# Sheet_2.net
KiCad netlist of a schematic drawn in Altium Designer
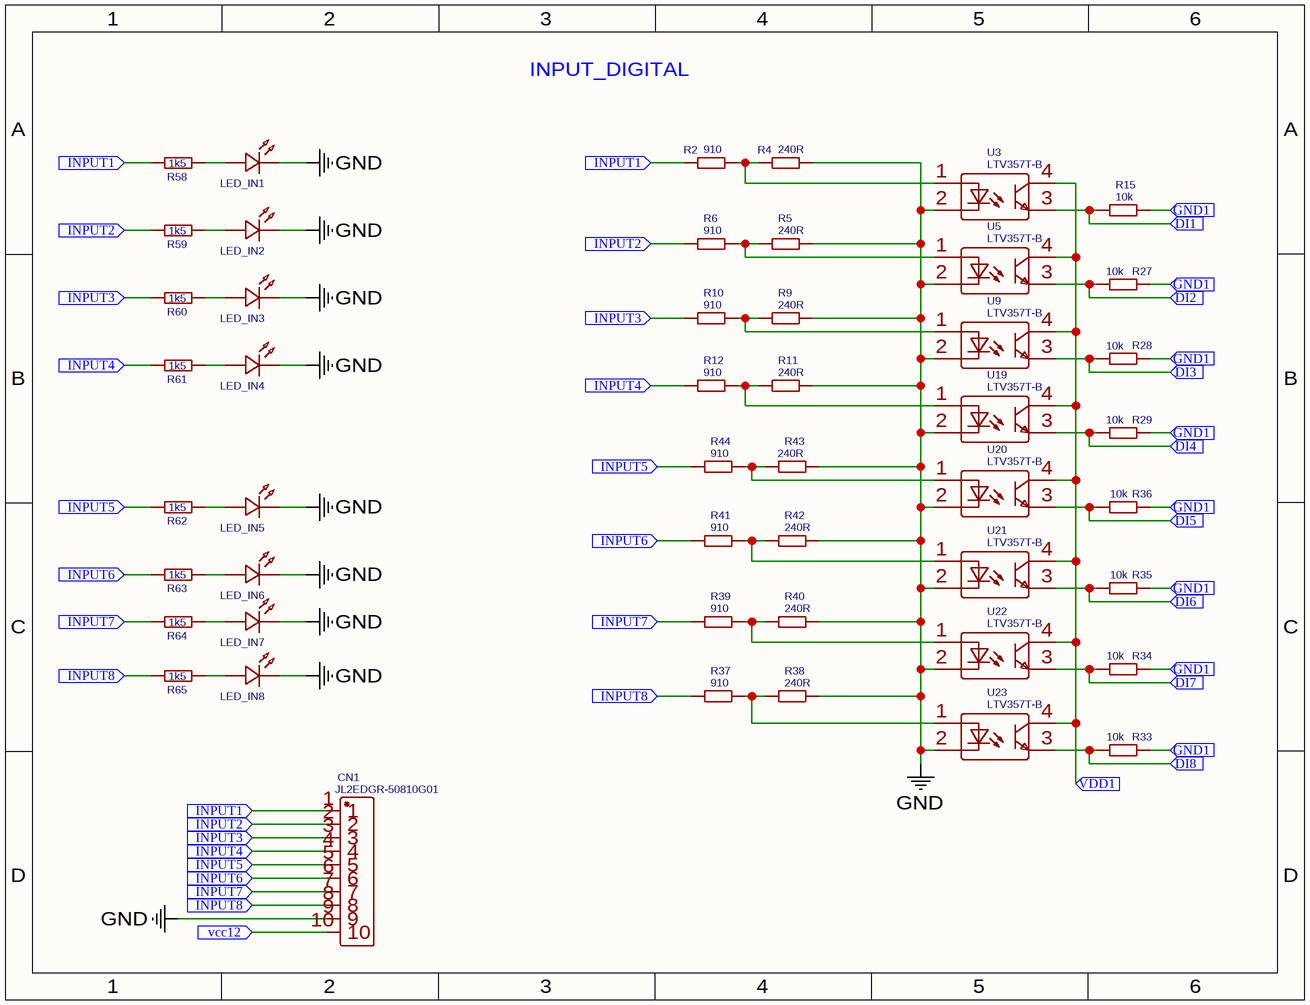
[diagram p0: Sheet_2.schdoc]

(export (version "E")
  (design (tool "Eeschema 10.0.6"))
  (components
    (comp (ref "CN1")
      (value "JL2EDGR-50810G01")
      (fields (field (name "BOM_SUPPLIER PART") "C424394") (field (name "CONTRIBUTOR") "LCSC"))
      (libsource (lib "altium-import") (part "root_0_JL2EDGR-50810G01_"))
    )
    (comp (ref "LED_IN1")
      (value "red")
      (fields
        (field (name "BOM_SUPPLIER PART") "C568941")
        (field (name "BOM_MANUFACTURER PART") "HL-503H3GD")
        (field (name "CONTRIBUTOR") "LCSC")
      )
      (libsource (lib "altium-import") (part "root_0_red_"))
    )
    (comp (ref "LED_IN2")
      (value "red")
      (fields
        (field (name "BOM_SUPPLIER PART") "C568941")
        (field (name "BOM_MANUFACTURER PART") "HL-503H3GD")
        (field (name "CONTRIBUTOR") "LCSC")
      )
      (libsource (lib "altium-import") (part "root_0_red_"))
    )
    (comp (ref "LED_IN3")
      (value "red")
      (fields
        (field (name "BOM_SUPPLIER PART") "C568941")
        (field (name "BOM_MANUFACTURER PART") "HL-503H3GD")
        (field (name "CONTRIBUTOR") "LCSC")
      )
      (libsource (lib "altium-import") (part "root_0_red_"))
    )
    (comp (ref "LED_IN4")
      (value "red")
      (fields
        (field (name "BOM_SUPPLIER PART") "C568941")
        (field (name "BOM_MANUFACTURER PART") "HL-503H3GD")
        (field (name "CONTRIBUTOR") "LCSC")
      )
      (libsource (lib "altium-import") (part "root_0_red_"))
    )
    (comp (ref "LED_IN5")
      (value "red")
      (fields
        (field (name "BOM_SUPPLIER PART") "C568941")
        (field (name "BOM_MANUFACTURER PART") "HL-503H3GD")
        (field (name "CONTRIBUTOR") "LCSC")
      )
      (libsource (lib "altium-import") (part "root_0_red_"))
    )
    (comp (ref "LED_IN6")
      (value "red")
      (fields
        (field (name "BOM_SUPPLIER PART") "C568941")
        (field (name "BOM_MANUFACTURER PART") "HL-503H3GD")
        (field (name "CONTRIBUTOR") "LCSC")
      )
      (libsource (lib "altium-import") (part "root_0_red_"))
    )
    (comp (ref "LED_IN7")
      (value "red")
      (fields
        (field (name "BOM_SUPPLIER PART") "C568941")
        (field (name "BOM_MANUFACTURER PART") "HL-503H3GD")
        (field (name "CONTRIBUTOR") "LCSC")
      )
      (libsource (lib "altium-import") (part "root_0_red_"))
    )
    (comp (ref "LED_IN8")
      (value "red")
      (fields
        (field (name "BOM_SUPPLIER PART") "C568941")
        (field (name "BOM_MANUFACTURER PART") "HL-503H3GD")
        (field (name "CONTRIBUTOR") "LCSC")
      )
      (libsource (lib "altium-import") (part "root_0_red_"))
    )
    (comp (ref "R2")
      (value "910")
      (fields (field (name "BOM_SUPPLIER PART") "C120038") (field (name "CONTRIBUTOR") "LCSC"))
      (libsource (lib "altium-import") (part "root_2_910_"))
    )
    (comp (ref "R4")
      (value "240R")
      (fields (field (name "BOM_SUPPLIER PART") "C120038") (field (name "CONTRIBUTOR") "LCSC"))
      (libsource (lib "altium-import") (part "root_2_240R_"))
    )
    (comp (ref "R5")
      (value "240R")
      (fields (field (name "BOM_SUPPLIER PART") "C120038") (field (name "CONTRIBUTOR") "LCSC"))
      (libsource (lib "altium-import") (part "root_2_240R_"))
    )
    (comp (ref "R6")
      (value "910")
      (fields (field (name "BOM_SUPPLIER PART") "C120038") (field (name "CONTRIBUTOR") "LCSC"))
      (libsource (lib "altium-import") (part "root_2_910_"))
    )
    (comp (ref "R9")
      (value "240R")
      (fields (field (name "BOM_SUPPLIER PART") "C120038") (field (name "CONTRIBUTOR") "LCSC"))
      (libsource (lib "altium-import") (part "root_2_240R_"))
    )
    (comp (ref "R10")
      (value "910")
      (fields (field (name "BOM_SUPPLIER PART") "C120038") (field (name "CONTRIBUTOR") "LCSC"))
      (libsource (lib "altium-import") (part "root_2_910_"))
    )
    (comp (ref "R11")
      (value "240R")
      (fields (field (name "BOM_SUPPLIER PART") "C120038") (field (name "CONTRIBUTOR") "LCSC"))
      (libsource (lib "altium-import") (part "root_2_240R_"))
    )
    (comp (ref "R12")
      (value "910")
      (fields (field (name "BOM_SUPPLIER PART") "C120038") (field (name "CONTRIBUTOR") "LCSC"))
      (libsource (lib "altium-import") (part "root_2_910_"))
    )
    (comp (ref "R15")
      (value "10k")
      (fields (field (name "BOM_SUPPLIER PART") "C120038") (field (name "CONTRIBUTOR") "LCSC"))
      (libsource (lib "altium-import") (part "root_2_10k_"))
    )
    (comp (ref "R27")
      (value "10k")
      (fields (field (name "BOM_SUPPLIER PART") "C120038") (field (name "CONTRIBUTOR") "LCSC"))
      (libsource (lib "altium-import") (part "root_2_10k_"))
    )
    (comp (ref "R28")
      (value "10k")
      (fields (field (name "BOM_SUPPLIER PART") "C120038") (field (name "CONTRIBUTOR") "LCSC"))
      (libsource (lib "altium-import") (part "root_2_10k_"))
    )
    (comp (ref "R29")
      (value "10k")
      (fields (field (name "BOM_SUPPLIER PART") "C120038") (field (name "CONTRIBUTOR") "LCSC"))
      (libsource (lib "altium-import") (part "root_2_10k_"))
    )
    (comp (ref "R33")
      (value "10k")
      (fields (field (name "BOM_SUPPLIER PART") "C120038") (field (name "CONTRIBUTOR") "LCSC"))
      (libsource (lib "altium-import") (part "root_2_10k_"))
    )
    (comp (ref "R34")
      (value "10k")
      (fields (field (name "BOM_SUPPLIER PART") "C120038") (field (name "CONTRIBUTOR") "LCSC"))
      (libsource (lib "altium-import") (part "root_2_10k_"))
    )
    (comp (ref "R35")
      (value "10k")
      (fields (field (name "BOM_SUPPLIER PART") "C120038") (field (name "CONTRIBUTOR") "LCSC"))
      (libsource (lib "altium-import") (part "root_2_10k_"))
    )
    (comp (ref "R36")
      (value "10k")
      (fields (field (name "BOM_SUPPLIER PART") "C120038") (field (name "CONTRIBUTOR") "LCSC"))
      (libsource (lib "altium-import") (part "root_2_10k_"))
    )
    (comp (ref "R37")
      (value "910")
      (fields (field (name "BOM_SUPPLIER PART") "C120038") (field (name "CONTRIBUTOR") "LCSC"))
      (libsource (lib "altium-import") (part "root_2_910_"))
    )
    (comp (ref "R38")
      (value "240R")
      (fields (field (name "BOM_SUPPLIER PART") "C120038") (field (name "CONTRIBUTOR") "LCSC"))
      (libsource (lib "altium-import") (part "root_2_240R_"))
    )
    (comp (ref "R39")
      (value "910")
      (fields (field (name "BOM_SUPPLIER PART") "C120038") (field (name "CONTRIBUTOR") "LCSC"))
      (libsource (lib "altium-import") (part "root_2_910_"))
    )
    (comp (ref "R40")
      (value "240R")
      (fields (field (name "BOM_SUPPLIER PART") "C120038") (field (name "CONTRIBUTOR") "LCSC"))
      (libsource (lib "altium-import") (part "root_2_240R_"))
    )
    (comp (ref "R41")
      (value "910")
      (fields (field (name "BOM_SUPPLIER PART") "C120038") (field (name "CONTRIBUTOR") "LCSC"))
      (libsource (lib "altium-import") (part "root_2_910_"))
    )
    (comp (ref "R42")
      (value "240R")
      (fields (field (name "BOM_SUPPLIER PART") "C120038") (field (name "CONTRIBUTOR") "LCSC"))
      (libsource (lib "altium-import") (part "root_2_240R_"))
    )
    (comp (ref "R43")
      (value "240R")
      (fields (field (name "BOM_SUPPLIER PART") "C120038") (field (name "CONTRIBUTOR") "LCSC"))
      (libsource (lib "altium-import") (part "root_2_240R_"))
    )
    (comp (ref "R44")
      (value "910")
      (fields (field (name "BOM_SUPPLIER PART") "C120038") (field (name "CONTRIBUTOR") "LCSC"))
      (libsource (lib "altium-import") (part "root_2_910_"))
    )
    (comp (ref "R58")
      (value "1k5")
      (fields (field (name "BOM_SUPPLIER PART") "C120038") (field (name "CONTRIBUTOR") "LCSC"))
      (libsource (lib "altium-import") (part "root_2_1k5_"))
    )
    (comp (ref "R59")
      (value "1k5")
      (fields (field (name "BOM_SUPPLIER PART") "C120038") (field (name "CONTRIBUTOR") "LCSC"))
      (libsource (lib "altium-import") (part "root_2_1k5_"))
    )
    (comp (ref "R60")
      (value "1k5")
      (fields (field (name "BOM_SUPPLIER PART") "C120038") (field (name "CONTRIBUTOR") "LCSC"))
      (libsource (lib "altium-import") (part "root_2_1k5_"))
    )
    (comp (ref "R61")
      (value "1k5")
      (fields (field (name "BOM_SUPPLIER PART") "C120038") (field (name "CONTRIBUTOR") "LCSC"))
      (libsource (lib "altium-import") (part "root_2_1k5_"))
    )
    (comp (ref "R62")
      (value "1k5")
      (fields (field (name "BOM_SUPPLIER PART") "C120038") (field (name "CONTRIBUTOR") "LCSC"))
      (libsource (lib "altium-import") (part "root_2_1k5_"))
    )
    (comp (ref "R63")
      (value "1k5")
      (fields (field (name "BOM_SUPPLIER PART") "C120038") (field (name "CONTRIBUTOR") "LCSC"))
      (libsource (lib "altium-import") (part "root_2_1k5_"))
    )
    (comp (ref "R64")
      (value "1k5")
      (fields (field (name "BOM_SUPPLIER PART") "C120038") (field (name "CONTRIBUTOR") "LCSC"))
      (libsource (lib "altium-import") (part "root_2_1k5_"))
    )
    (comp (ref "R65")
      (value "1k5")
      (fields (field (name "BOM_SUPPLIER PART") "C120038") (field (name "CONTRIBUTOR") "LCSC"))
      (libsource (lib "altium-import") (part "root_2_1k5_"))
    )
    (comp (ref "U3")
      (value "LTV357T-B")
      (fields (field (name "BOM_SUPPLIER PART") "C33068") (field (name "CONTRIBUTOR") "LCSC"))
      (libsource (lib "altium-import") (part "root_0_LTV357T-B_"))
    )
    (comp (ref "U5")
      (value "LTV357T-B")
      (fields (field (name "BOM_SUPPLIER PART") "C33068") (field (name "CONTRIBUTOR") "LCSC"))
      (libsource (lib "altium-import") (part "root_0_LTV357T-B_"))
    )
    (comp (ref "U9")
      (value "LTV357T-B")
      (fields (field (name "BOM_SUPPLIER PART") "C33068") (field (name "CONTRIBUTOR") "LCSC"))
      (libsource (lib "altium-import") (part "root_0_LTV357T-B_"))
    )
    (comp (ref "U19")
      (value "LTV357T-B")
      (fields (field (name "BOM_SUPPLIER PART") "C33068") (field (name "CONTRIBUTOR") "LCSC"))
      (libsource (lib "altium-import") (part "root_0_LTV357T-B_"))
    )
    (comp (ref "U20")
      (value "LTV357T-B")
      (fields (field (name "BOM_SUPPLIER PART") "C33068") (field (name "CONTRIBUTOR") "LCSC"))
      (libsource (lib "altium-import") (part "root_0_LTV357T-B_"))
    )
    (comp (ref "U21")
      (value "LTV357T-B")
      (fields (field (name "BOM_SUPPLIER PART") "C33068") (field (name "CONTRIBUTOR") "LCSC"))
      (libsource (lib "altium-import") (part "root_0_LTV357T-B_"))
    )
    (comp (ref "U22")
      (value "LTV357T-B")
      (fields (field (name "BOM_SUPPLIER PART") "C33068") (field (name "CONTRIBUTOR") "LCSC"))
      (libsource (lib "altium-import") (part "root_0_LTV357T-B_"))
    )
    (comp (ref "U23")
      (value "LTV357T-B")
      (fields (field (name "BOM_SUPPLIER PART") "C33068") (field (name "CONTRIBUTOR") "LCSC"))
      (libsource (lib "altium-import") (part "root_0_LTV357T-B_"))
    )
  )
  (nets
    (net (code "1") (name "/DI1") (class "Default")
      (node (ref "R15") (pin "2") (pinfunction "2_2") (pintype "passive"))
      (node (ref "U3") (pin "3") (pinfunction "3_3") (pintype "passive"))
    )
    (net (code "2") (name "/DI2") (class "Default")
      (node (ref "R27") (pin "2") (pinfunction "2_2") (pintype "passive"))
      (node (ref "U5") (pin "3") (pinfunction "3_3") (pintype "passive"))
    )
    (net (code "3") (name "/DI3") (class "Default")
      (node (ref "R28") (pin "2") (pinfunction "2_2") (pintype "passive"))
      (node (ref "U9") (pin "3") (pinfunction "3_3") (pintype "passive"))
    )
    (net (code "4") (name "/DI4") (class "Default")
      (node (ref "R29") (pin "2") (pinfunction "2_2") (pintype "passive"))
      (node (ref "U19") (pin "3") (pinfunction "3_3") (pintype "passive"))
    )
    (net (code "5") (name "/DI5") (class "Default")
      (node (ref "R36") (pin "2") (pinfunction "2_2") (pintype "passive"))
      (node (ref "U20") (pin "3") (pinfunction "3_3") (pintype "passive"))
    )
    (net (code "6") (name "/DI6") (class "Default")
      (node (ref "R35") (pin "2") (pinfunction "2_2") (pintype "passive"))
      (node (ref "U21") (pin "3") (pinfunction "3_3") (pintype "passive"))
    )
    (net (code "7") (name "/DI7") (class "Default")
      (node (ref "R34") (pin "2") (pinfunction "2_2") (pintype "passive"))
      (node (ref "U22") (pin "3") (pinfunction "3_3") (pintype "passive"))
    )
    (net (code "8") (name "/DI8") (class "Default")
      (node (ref "R33") (pin "2") (pinfunction "2_2") (pintype "passive"))
      (node (ref "U23") (pin "3") (pinfunction "3_3") (pintype "passive"))
    )
    (net (code "9") (name "/GND1") (class "Default")
      (node (ref "R15") (pin "1") (pinfunction "1_1") (pintype "passive"))
      (node (ref "R27") (pin "1") (pinfunction "1_1") (pintype "passive"))
      (node (ref "R28") (pin "1") (pinfunction "1_1") (pintype "passive"))
      (node (ref "R29") (pin "1") (pinfunction "1_1") (pintype "passive"))
      (node (ref "R33") (pin "1") (pinfunction "1_1") (pintype "passive"))
      (node (ref "R34") (pin "1") (pinfunction "1_1") (pintype "passive"))
      (node (ref "R35") (pin "1") (pinfunction "1_1") (pintype "passive"))
      (node (ref "R36") (pin "1") (pinfunction "1_1") (pintype "passive"))
    )
    (net (code "10") (name "/INPUT1") (class "Default")
      (node (ref "CN1") (pin "1") (pinfunction "1_1") (pintype "passive"))
      (node (ref "R2") (pin "2") (pinfunction "2_2") (pintype "passive"))
      (node (ref "R58") (pin "2") (pinfunction "2_2") (pintype "passive"))
    )
    (net (code "11") (name "/INPUT2") (class "Default")
      (node (ref "CN1") (pin "2") (pinfunction "2_2") (pintype "passive"))
      (node (ref "R59") (pin "2") (pinfunction "2_2") (pintype "passive"))
      (node (ref "R6") (pin "2") (pinfunction "2_2") (pintype "passive"))
    )
    (net (code "12") (name "/INPUT3") (class "Default")
      (node (ref "CN1") (pin "3") (pinfunction "3_3") (pintype "passive"))
      (node (ref "R10") (pin "2") (pinfunction "2_2") (pintype "passive"))
      (node (ref "R60") (pin "2") (pinfunction "2_2") (pintype "passive"))
    )
    (net (code "13") (name "/INPUT4") (class "Default")
      (node (ref "CN1") (pin "4") (pinfunction "4_4") (pintype "passive"))
      (node (ref "R12") (pin "2") (pinfunction "2_2") (pintype "passive"))
      (node (ref "R61") (pin "2") (pinfunction "2_2") (pintype "passive"))
    )
    (net (code "14") (name "/INPUT5") (class "Default")
      (node (ref "CN1") (pin "5") (pinfunction "5_5") (pintype "passive"))
      (node (ref "R44") (pin "2") (pinfunction "2_2") (pintype "passive"))
      (node (ref "R62") (pin "2") (pinfunction "2_2") (pintype "passive"))
    )
    (net (code "15") (name "/INPUT6") (class "Default")
      (node (ref "CN1") (pin "6") (pinfunction "6_6") (pintype "passive"))
      (node (ref "R41") (pin "2") (pinfunction "2_2") (pintype "passive"))
      (node (ref "R63") (pin "2") (pinfunction "2_2") (pintype "passive"))
    )
    (net (code "16") (name "/INPUT7") (class "Default")
      (node (ref "CN1") (pin "7") (pinfunction "7_7") (pintype "passive"))
      (node (ref "R39") (pin "2") (pinfunction "2_2") (pintype "passive"))
      (node (ref "R64") (pin "2") (pinfunction "2_2") (pintype "passive"))
    )
    (net (code "17") (name "/INPUT8") (class "Default")
      (node (ref "CN1") (pin "8") (pinfunction "8_8") (pintype "passive"))
      (node (ref "R37") (pin "2") (pinfunction "2_2") (pintype "passive"))
      (node (ref "R65") (pin "2") (pinfunction "2_2") (pintype "passive"))
    )
    (net (code "18") (name "/VDD1") (class "Default")
      (node (ref "U19") (pin "4") (pinfunction "4_4") (pintype "passive"))
      (node (ref "U20") (pin "4") (pinfunction "4_4") (pintype "passive"))
      (node (ref "U21") (pin "4") (pinfunction "4_4") (pintype "passive"))
      (node (ref "U22") (pin "4") (pinfunction "4_4") (pintype "passive"))
      (node (ref "U23") (pin "4") (pinfunction "4_4") (pintype "passive"))
      (node (ref "U3") (pin "4") (pinfunction "4_4") (pintype "passive"))
      (node (ref "U5") (pin "4") (pinfunction "4_4") (pintype "passive"))
      (node (ref "U9") (pin "4") (pinfunction "4_4") (pintype "passive"))
    )
    (net (code "19") (name "/vcc12") (class "Default")
      (node (ref "CN1") (pin "10") (pinfunction "10_10") (pintype "passive"))
    )
    (net (code "20") (name "GND") (class "Default")
      (node (ref "CN1") (pin "9") (pinfunction "9_9") (pintype "passive"))
      (node (ref "LED_IN1") (pin "2") (pinfunction "2_2") (pintype "passive"))
      (node (ref "LED_IN2") (pin "2") (pinfunction "2_2") (pintype "passive"))
      (node (ref "LED_IN3") (pin "2") (pinfunction "2_2") (pintype "passive"))
      (node (ref "LED_IN4") (pin "2") (pinfunction "2_2") (pintype "passive"))
      (node (ref "LED_IN5") (pin "2") (pinfunction "2_2") (pintype "passive"))
      (node (ref "LED_IN6") (pin "2") (pinfunction "2_2") (pintype "passive"))
      (node (ref "LED_IN7") (pin "2") (pinfunction "2_2") (pintype "passive"))
      (node (ref "LED_IN8") (pin "2") (pinfunction "2_2") (pintype "passive"))
      (node (ref "R11") (pin "1") (pinfunction "1_1") (pintype "passive"))
      (node (ref "R38") (pin "1") (pinfunction "1_1") (pintype "passive"))
      (node (ref "R4") (pin "1") (pinfunction "1_1") (pintype "passive"))
      (node (ref "R40") (pin "1") (pinfunction "1_1") (pintype "passive"))
      (node (ref "R42") (pin "1") (pinfunction "1_1") (pintype "passive"))
      (node (ref "R43") (pin "1") (pinfunction "1_1") (pintype "passive"))
      (node (ref "R5") (pin "1") (pinfunction "1_1") (pintype "passive"))
      (node (ref "R9") (pin "1") (pinfunction "1_1") (pintype "passive"))
      (node (ref "U19") (pin "2") (pinfunction "2_2") (pintype "passive"))
      (node (ref "U20") (pin "2") (pinfunction "2_2") (pintype "passive"))
      (node (ref "U21") (pin "2") (pinfunction "2_2") (pintype "passive"))
      (node (ref "U22") (pin "2") (pinfunction "2_2") (pintype "passive"))
      (node (ref "U23") (pin "2") (pinfunction "2_2") (pintype "passive"))
      (node (ref "U3") (pin "2") (pinfunction "2_2") (pintype "passive"))
      (node (ref "U5") (pin "2") (pinfunction "2_2") (pintype "passive"))
      (node (ref "U9") (pin "2") (pinfunction "2_2") (pintype "passive"))
    )
    (net (code "21") (name "Net-(LED_IN1-Pad1)") (class "Default")
      (node (ref "LED_IN1") (pin "1") (pinfunction "1_1") (pintype "passive"))
      (node (ref "R58") (pin "1") (pinfunction "1_1") (pintype "passive"))
    )
    (net (code "22") (name "Net-(LED_IN2-Pad1)") (class "Default")
      (node (ref "LED_IN2") (pin "1") (pinfunction "1_1") (pintype "passive"))
      (node (ref "R59") (pin "1") (pinfunction "1_1") (pintype "passive"))
    )
    (net (code "23") (name "Net-(LED_IN3-Pad1)") (class "Default")
      (node (ref "LED_IN3") (pin "1") (pinfunction "1_1") (pintype "passive"))
      (node (ref "R60") (pin "1") (pinfunction "1_1") (pintype "passive"))
    )
    (net (code "24") (name "Net-(LED_IN4-Pad1)") (class "Default")
      (node (ref "LED_IN4") (pin "1") (pinfunction "1_1") (pintype "passive"))
      (node (ref "R61") (pin "1") (pinfunction "1_1") (pintype "passive"))
    )
    (net (code "25") (name "Net-(LED_IN5-Pad1)") (class "Default")
      (node (ref "LED_IN5") (pin "1") (pinfunction "1_1") (pintype "passive"))
      (node (ref "R62") (pin "1") (pinfunction "1_1") (pintype "passive"))
    )
    (net (code "26") (name "Net-(LED_IN6-Pad1)") (class "Default")
      (node (ref "LED_IN6") (pin "1") (pinfunction "1_1") (pintype "passive"))
      (node (ref "R63") (pin "1") (pinfunction "1_1") (pintype "passive"))
    )
    (net (code "27") (name "Net-(LED_IN7-Pad1)") (class "Default")
      (node (ref "LED_IN7") (pin "1") (pinfunction "1_1") (pintype "passive"))
      (node (ref "R64") (pin "1") (pinfunction "1_1") (pintype "passive"))
    )
    (net (code "28") (name "Net-(LED_IN8-Pad1)") (class "Default")
      (node (ref "LED_IN8") (pin "1") (pinfunction "1_1") (pintype "passive"))
      (node (ref "R65") (pin "1") (pinfunction "1_1") (pintype "passive"))
    )
    (net (code "29") (name "Net-(R2-Pad1)") (class "Default")
      (node (ref "R2") (pin "1") (pinfunction "1_1") (pintype "passive"))
      (node (ref "R4") (pin "2") (pinfunction "2_2") (pintype "passive"))
      (node (ref "U3") (pin "1") (pinfunction "1_1") (pintype "passive"))
    )
    (net (code "30") (name "Net-(R5-Pad2)") (class "Default")
      (node (ref "R5") (pin "2") (pinfunction "2_2") (pintype "passive"))
      (node (ref "R6") (pin "1") (pinfunction "1_1") (pintype "passive"))
      (node (ref "U5") (pin "1") (pinfunction "1_1") (pintype "passive"))
    )
    (net (code "31") (name "Net-(R10-Pad1)") (class "Default")
      (node (ref "R10") (pin "1") (pinfunction "1_1") (pintype "passive"))
      (node (ref "R9") (pin "2") (pinfunction "2_2") (pintype "passive"))
      (node (ref "U9") (pin "1") (pinfunction "1_1") (pintype "passive"))
    )
    (net (code "32") (name "Net-(R11-Pad2)") (class "Default")
      (node (ref "R11") (pin "2") (pinfunction "2_2") (pintype "passive"))
      (node (ref "R12") (pin "1") (pinfunction "1_1") (pintype "passive"))
      (node (ref "U19") (pin "1") (pinfunction "1_1") (pintype "passive"))
    )
    (net (code "33") (name "Net-(R37-Pad1)") (class "Default")
      (node (ref "R37") (pin "1") (pinfunction "1_1") (pintype "passive"))
      (node (ref "R38") (pin "2") (pinfunction "2_2") (pintype "passive"))
      (node (ref "U23") (pin "1") (pinfunction "1_1") (pintype "passive"))
    )
    (net (code "34") (name "Net-(R39-Pad1)") (class "Default")
      (node (ref "R39") (pin "1") (pinfunction "1_1") (pintype "passive"))
      (node (ref "R40") (pin "2") (pinfunction "2_2") (pintype "passive"))
      (node (ref "U22") (pin "1") (pinfunction "1_1") (pintype "passive"))
    )
    (net (code "35") (name "Net-(R41-Pad1)") (class "Default")
      (node (ref "R41") (pin "1") (pinfunction "1_1") (pintype "passive"))
      (node (ref "R42") (pin "2") (pinfunction "2_2") (pintype "passive"))
      (node (ref "U21") (pin "1") (pinfunction "1_1") (pintype "passive"))
    )
    (net (code "36") (name "Net-(R43-Pad2)") (class "Default")
      (node (ref "R43") (pin "2") (pinfunction "2_2") (pintype "passive"))
      (node (ref "R44") (pin "1") (pinfunction "1_1") (pintype "passive"))
      (node (ref "U20") (pin "1") (pinfunction "1_1") (pintype "passive"))
    )
  )
)
